# Analog_Input.net
KiCad netlist of a schematic drawn in Altium Designer
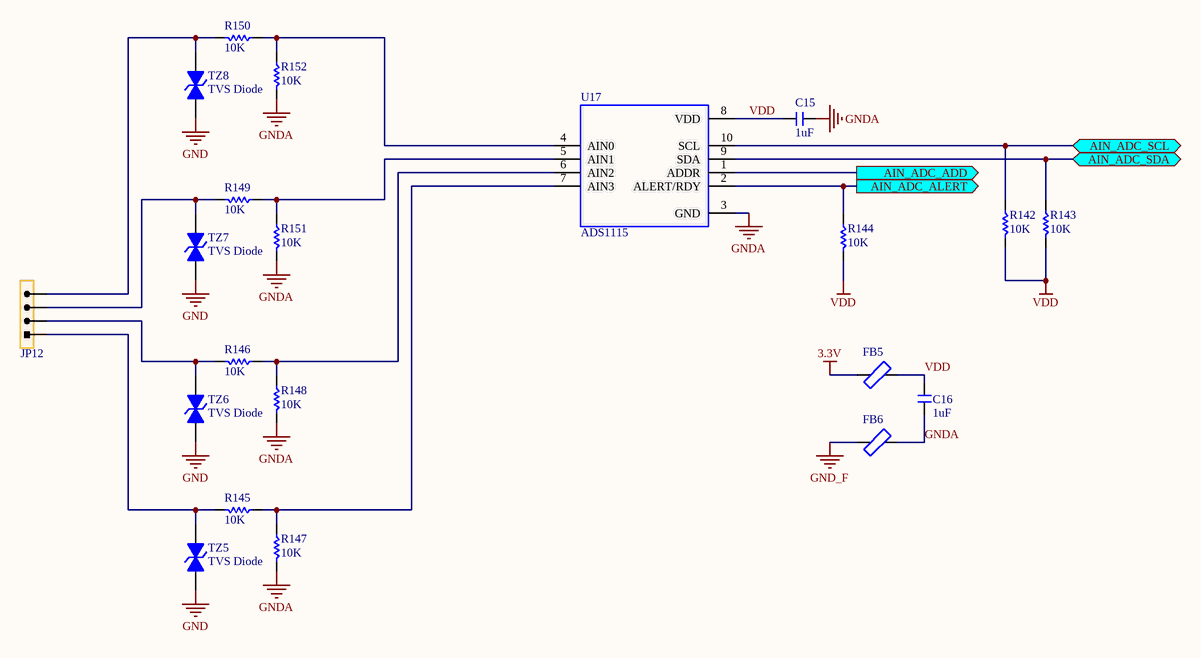
[diagram p0: Analog Input.SchDoc]

(export (version "E")
  (design (tool "Eeschema 10.0.6"))
  (components
    (comp (ref "C15")
      (value "1uF")
      (footprint "C 0805")
      (description "Non-polar patch capacitor")
      (fields (field (name "版权归属") "源创客"))
      (libsource (lib "Passive (Resistor-Capacitor-Inductor-Veristor-Ferrite)") (part "C"))
    )
    (comp (ref "C16")
      (value "1uF")
      (footprint "C 0805")
      (description "Non-polar patch capacitor")
      (fields (field (name "版权归属") "源创客"))
      (libsource (lib "Passive (Resistor-Capacitor-Inductor-Veristor-Ferrite)") (part "C"))
    )
    (comp (ref "FB5")
      (value "~")
      (footprint "F 0805")
      (description "Ferrite Bead")
      (fields (field (name "版权归属") "源创客"))
      (libsource (lib "Passive (Resistor-Capacitor-Inductor-Veristor-Ferrite)") (part "FB"))
    )
    (comp (ref "FB6")
      (value "~")
      (footprint "F 0805")
      (description "Ferrite Bead")
      (fields (field (name "版权归属") "源创客"))
      (libsource (lib "Passive (Resistor-Capacitor-Inductor-Veristor-Ferrite)") (part "FB"))
    )
    (comp (ref "JP12")
      (value "HDR-1X4")
      (footprint "KF-4P-BLK-H-3.81")
      (description "4P Connector")
      (fields (field (name "版权归属") "源创客"))
      (libsource (lib "Connectors") (part "Header 4"))
    )
    (comp (ref "R142")
      (value "10K")
      (footprint "R 0805")
      (description "Chip resistor")
      (fields (field (name "版权归属") "源创客"))
      (libsource (lib "Passive (Resistor-Capacitor-Inductor-Veristor-Ferrite)") (part "R"))
    )
    (comp (ref "R143")
      (value "10K")
      (footprint "R 0805")
      (description "Chip resistor")
      (fields (field (name "版权归属") "源创客"))
      (libsource (lib "Passive (Resistor-Capacitor-Inductor-Veristor-Ferrite)") (part "R"))
    )
    (comp (ref "R144")
      (value "10K")
      (footprint "R 0805")
      (description "Chip resistor")
      (fields (field (name "版权归属") "源创客"))
      (libsource (lib "Passive (Resistor-Capacitor-Inductor-Veristor-Ferrite)") (part "R"))
    )
    (comp (ref "R145")
      (value "10K")
      (footprint "R 0805")
      (description "Chip resistor")
      (fields (field (name "版权归属") "源创客"))
      (libsource (lib "Passive (Resistor-Capacitor-Inductor-Veristor-Ferrite)") (part "R"))
    )
    (comp (ref "R146")
      (value "10K")
      (footprint "R 0805")
      (description "Chip resistor")
      (fields (field (name "版权归属") "源创客"))
      (libsource (lib "Passive (Resistor-Capacitor-Inductor-Veristor-Ferrite)") (part "R"))
    )
    (comp (ref "R147")
      (value "10K")
      (footprint "R 0805")
      (description "Chip resistor")
      (fields (field (name "版权归属") "源创客"))
      (libsource (lib "Passive (Resistor-Capacitor-Inductor-Veristor-Ferrite)") (part "R"))
    )
    (comp (ref "R148")
      (value "10K")
      (footprint "R 0805")
      (description "Chip resistor")
      (fields (field (name "版权归属") "源创客"))
      (libsource (lib "Passive (Resistor-Capacitor-Inductor-Veristor-Ferrite)") (part "R"))
    )
    (comp (ref "R149")
      (value "10K")
      (footprint "R 0805")
      (description "Chip resistor")
      (fields (field (name "版权归属") "源创客"))
      (libsource (lib "Passive (Resistor-Capacitor-Inductor-Veristor-Ferrite)") (part "R"))
    )
    (comp (ref "R150")
      (value "10K")
      (footprint "R 0805")
      (description "Chip resistor")
      (fields (field (name "版权归属") "源创客"))
      (libsource (lib "Passive (Resistor-Capacitor-Inductor-Veristor-Ferrite)") (part "R"))
    )
    (comp (ref "R151")
      (value "10K")
      (footprint "R 0805")
      (description "Chip resistor")
      (fields (field (name "版权归属") "源创客"))
      (libsource (lib "Passive (Resistor-Capacitor-Inductor-Veristor-Ferrite)") (part "R"))
    )
    (comp (ref "R152")
      (value "10K")
      (footprint "R 0805")
      (description "Chip resistor")
      (fields (field (name "版权归属") "源创客"))
      (libsource (lib "Passive (Resistor-Capacitor-Inductor-Veristor-Ferrite)") (part "R"))
    )
    (comp (ref "TZ5")
      (value "TVS Diode")
      (footprint "SMB")
      (description "Surface Mount TRANSZORB® Transient Voltage Suppressors")
      (libsource (lib "Diode-Zener-Rectifier Bridge") (part "SMBJ-CA"))
    )
    (comp (ref "TZ6")
      (value "TVS Diode")
      (footprint "SMB")
      (description "Surface Mount TRANSZORB® Transient Voltage Suppressors")
      (libsource (lib "Diode-Zener-Rectifier Bridge") (part "SMBJ-CA"))
    )
    (comp (ref "TZ7")
      (value "TVS Diode")
      (footprint "SMB")
      (description "Surface Mount TRANSZORB® Transient Voltage Suppressors")
      (libsource (lib "Diode-Zener-Rectifier Bridge") (part "SMBJ-CA"))
    )
    (comp (ref "TZ8")
      (value "TVS Diode")
      (footprint "SMB")
      (description "Surface Mount TRANSZORB® Transient Voltage Suppressors")
      (libsource (lib "Diode-Zener-Rectifier Bridge") (part "SMBJ-CA"))
    )
    (comp (ref "U17")
      (value "ADS1115")
      (footprint "VSSOP10-N")
      (fields (field (name "版权归属") "源创客"))
      (libsource (lib "Integrated Circuit") (part "ADS1115"))
    )
  )
  (nets
    (net (code "1") (name "/AIN_ADC_ADD") (class "Default")
      (node (ref "U17") (pin "1") (pinfunction "ADDR_1") (pintype "passive"))
    )
    (net (code "2") (name "/AIN_ADC_ALERT") (class "Default")
      (node (ref "R144") (pin "1") (pinfunction "1_1") (pintype "passive"))
      (node (ref "U17") (pin "2") (pinfunction "ALERT/RDY_2") (pintype "passive"))
    )
    (net (code "3") (name "/AIN_ADC_SCL") (class "Default")
      (node (ref "R142") (pin "1") (pinfunction "1_1") (pintype "passive"))
      (node (ref "U17") (pin "10") (pinfunction "SCL_10") (pintype "passive"))
    )
    (net (code "4") (name "/AIN_ADC_SDA") (class "Default")
      (node (ref "R143") (pin "1") (pinfunction "1_1") (pintype "passive"))
      (node (ref "U17") (pin "9") (pinfunction "SDA_9") (pintype "passive"))
    )
    (net (code "5") (name "3.3V") (class "Default")
      (node (ref "FB5") (pin "1") (pinfunction "1_1") (pintype "passive"))
    )
    (net (code "6") (name "GND") (class "Default")
      (node (ref "TZ5") (pin "1") (pinfunction "A_1") (pintype "passive"))
      (node (ref "TZ6") (pin "1") (pinfunction "A_1") (pintype "passive"))
      (node (ref "TZ7") (pin "1") (pinfunction "A_1") (pintype "passive"))
      (node (ref "TZ8") (pin "1") (pinfunction "A_1") (pintype "passive"))
    )
    (net (code "7") (name "GNDA") (class "Default")
      (node (ref "C15") (pin "1") (pinfunction "1_1") (pintype "passive"))
      (node (ref "C16") (pin "1") (pinfunction "1_1") (pintype "passive"))
      (node (ref "FB6") (pin "2") (pinfunction "2_2") (pintype "passive"))
      (node (ref "R147") (pin "2") (pinfunction "2_2") (pintype "passive"))
      (node (ref "R148") (pin "2") (pinfunction "2_2") (pintype "passive"))
      (node (ref "R151") (pin "2") (pinfunction "2_2") (pintype "passive"))
      (node (ref "R152") (pin "2") (pinfunction "2_2") (pintype "passive"))
      (node (ref "U17") (pin "3") (pinfunction "GND_3") (pintype "passive"))
    )
    (net (code "8") (name "GND_F") (class "Default")
      (node (ref "FB6") (pin "1") (pinfunction "1_1") (pintype "passive"))
    )
    (net (code "9") (name "Net-(TZ5-K)") (class "Default")
      (node (ref "JP12") (pin "1") (pintype "passive"))
      (node (ref "R145") (pin "2") (pinfunction "2_2") (pintype "passive"))
      (node (ref "TZ5") (pin "2") (pinfunction "K_2") (pintype "passive"))
    )
    (net (code "10") (name "Net-(TZ6-K)") (class "Default")
      (node (ref "JP12") (pin "2") (pintype "passive"))
      (node (ref "R146") (pin "2") (pinfunction "2_2") (pintype "passive"))
      (node (ref "TZ6") (pin "2") (pinfunction "K_2") (pintype "passive"))
    )
    (net (code "11") (name "Net-(TZ7-K)") (class "Default")
      (node (ref "JP12") (pin "3") (pintype "passive"))
      (node (ref "R149") (pin "2") (pinfunction "2_2") (pintype "passive"))
      (node (ref "TZ7") (pin "2") (pinfunction "K_2") (pintype "passive"))
    )
    (net (code "12") (name "Net-(TZ8-K)") (class "Default")
      (node (ref "JP12") (pin "4") (pintype "passive"))
      (node (ref "R150") (pin "2") (pinfunction "2_2") (pintype "passive"))
      (node (ref "TZ8") (pin "2") (pinfunction "K_2") (pintype "passive"))
    )
    (net (code "13") (name "Net-(U17-AIN0)") (class "Default")
      (node (ref "R150") (pin "1") (pinfunction "1_1") (pintype "passive"))
      (node (ref "R152") (pin "1") (pinfunction "1_1") (pintype "passive"))
      (node (ref "U17") (pin "4") (pinfunction "AIN0_4") (pintype "passive"))
    )
    (net (code "14") (name "Net-(U17-AIN1)") (class "Default")
      (node (ref "R149") (pin "1") (pinfunction "1_1") (pintype "passive"))
      (node (ref "R151") (pin "1") (pinfunction "1_1") (pintype "passive"))
      (node (ref "U17") (pin "5") (pinfunction "AIN1_5") (pintype "passive"))
    )
    (net (code "15") (name "Net-(U17-AIN2)") (class "Default")
      (node (ref "R146") (pin "1") (pinfunction "1_1") (pintype "passive"))
      (node (ref "R148") (pin "1") (pinfunction "1_1") (pintype "passive"))
      (node (ref "U17") (pin "6") (pinfunction "AIN2_6") (pintype "passive"))
    )
    (net (code "16") (name "Net-(U17-AIN3)") (class "Default")
      (node (ref "R145") (pin "1") (pinfunction "1_1") (pintype "passive"))
      (node (ref "R147") (pin "1") (pinfunction "1_1") (pintype "passive"))
      (node (ref "U17") (pin "7") (pinfunction "AIN3_7") (pintype "passive"))
    )
    (net (code "17") (name "VDD") (class "Default")
      (node (ref "C15") (pin "2") (pinfunction "2_2") (pintype "passive"))
      (node (ref "C16") (pin "2") (pinfunction "2_2") (pintype "passive"))
      (node (ref "FB5") (pin "2") (pinfunction "2_2") (pintype "passive"))
      (node (ref "R142") (pin "2") (pinfunction "2_2") (pintype "passive"))
      (node (ref "R143") (pin "2") (pinfunction "2_2") (pintype "passive"))
      (node (ref "R144") (pin "2") (pinfunction "2_2") (pintype "passive"))
      (node (ref "U17") (pin "8") (pinfunction "VDD_8") (pintype "passive"))
    )
  )
)
